# MaleHeader.net
KiCad netlist of a schematic drawn in Altium Designer
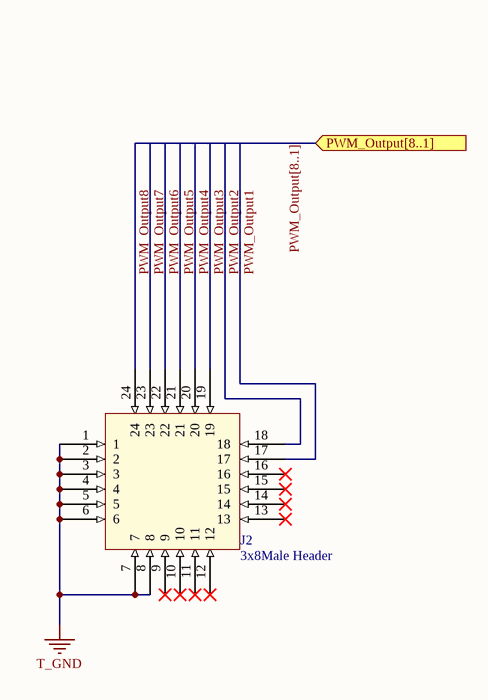
[diagram p0: MaleHeader.SchDoc]

(export (version "E")
  (design (tool "Eeschema 10.0.6"))
  (components
    (comp (ref "J2")
      (value "3x8Male Header")
      (footprint "3x8 Male Header")
      (description "3x8 male header")
      (libsource (lib "3x8 Male Header") (part "3x8Male Header"))
    )
  )
  (nets
    (net (code "1") (name "/PWM_Output1") (class "Default")
      (node (ref "J2") (pin "17") (pinfunction "17_17") (pintype "input"))
    )
    (net (code "2") (name "/PWM_Output2") (class "Default")
      (node (ref "J2") (pin "18") (pinfunction "18_18") (pintype "input"))
    )
    (net (code "3") (name "/PWM_Output3") (class "Default")
      (node (ref "J2") (pin "19") (pinfunction "19_19") (pintype "input"))
    )
    (net (code "4") (name "/PWM_Output4") (class "Default")
      (node (ref "J2") (pin "20") (pinfunction "20_20") (pintype "input"))
    )
    (net (code "5") (name "/PWM_Output5") (class "Default")
      (node (ref "J2") (pin "21") (pinfunction "21_21") (pintype "input"))
    )
    (net (code "6") (name "/PWM_Output6") (class "Default")
      (node (ref "J2") (pin "22") (pinfunction "22_22") (pintype "input"))
    )
    (net (code "7") (name "/PWM_Output7") (class "Default")
      (node (ref "J2") (pin "23") (pinfunction "23_23") (pintype "input"))
    )
    (net (code "8") (name "/PWM_Output8") (class "Default")
      (node (ref "J2") (pin "24") (pinfunction "24_24") (pintype "input"))
    )
    (net (code "10") (name "T_GND") (class "Default")
      (node (ref "J2") (pin "1") (pinfunction "1_1") (pintype "input"))
      (node (ref "J2") (pin "2") (pinfunction "2_2") (pintype "input"))
      (node (ref "J2") (pin "3") (pinfunction "3_3") (pintype "input"))
      (node (ref "J2") (pin "4") (pinfunction "4_4") (pintype "input"))
      (node (ref "J2") (pin "5") (pinfunction "5_5") (pintype "input"))
      (node (ref "J2") (pin "6") (pinfunction "6_6") (pintype "input"))
      (node (ref "J2") (pin "7") (pinfunction "7_7") (pintype "input"))
      (node (ref "J2") (pin "8") (pinfunction "8_8") (pintype "input"))
    )
    (net (code "11") (name "unconnected-(J2-Pad9)") (class "Default")
      (node (ref "J2") (pin "9") (pinfunction "9_9") (pintype "input+no_connect"))
    )
    (net (code "12") (name "unconnected-(J2-Pad10)") (class "Default")
      (node (ref "J2") (pin "10") (pinfunction "10_10") (pintype "input+no_connect"))
    )
    (net (code "13") (name "unconnected-(J2-Pad11)") (class "Default")
      (node (ref "J2") (pin "11") (pinfunction "11_11") (pintype "input+no_connect"))
    )
    (net (code "14") (name "unconnected-(J2-Pad12)") (class "Default")
      (node (ref "J2") (pin "12") (pinfunction "12_12") (pintype "input+no_connect"))
    )
    (net (code "15") (name "unconnected-(J2-Pad13)") (class "Default")
      (node (ref "J2") (pin "13") (pinfunction "13_13") (pintype "input+no_connect"))
    )
    (net (code "16") (name "unconnected-(J2-Pad14)") (class "Default")
      (node (ref "J2") (pin "14") (pinfunction "14_14") (pintype "input+no_connect"))
    )
    (net (code "17") (name "unconnected-(J2-Pad15)") (class "Default")
      (node (ref "J2") (pin "15") (pinfunction "15_15") (pintype "input+no_connect"))
    )
    (net (code "18") (name "unconnected-(J2-Pad16)") (class "Default")
      (node (ref "J2") (pin "16") (pinfunction "16_16") (pintype "input+no_connect"))
    )
  )
)
